# LPCOSensor3vValve.net
KiCad netlist of a schematic drawn in Altium Designer
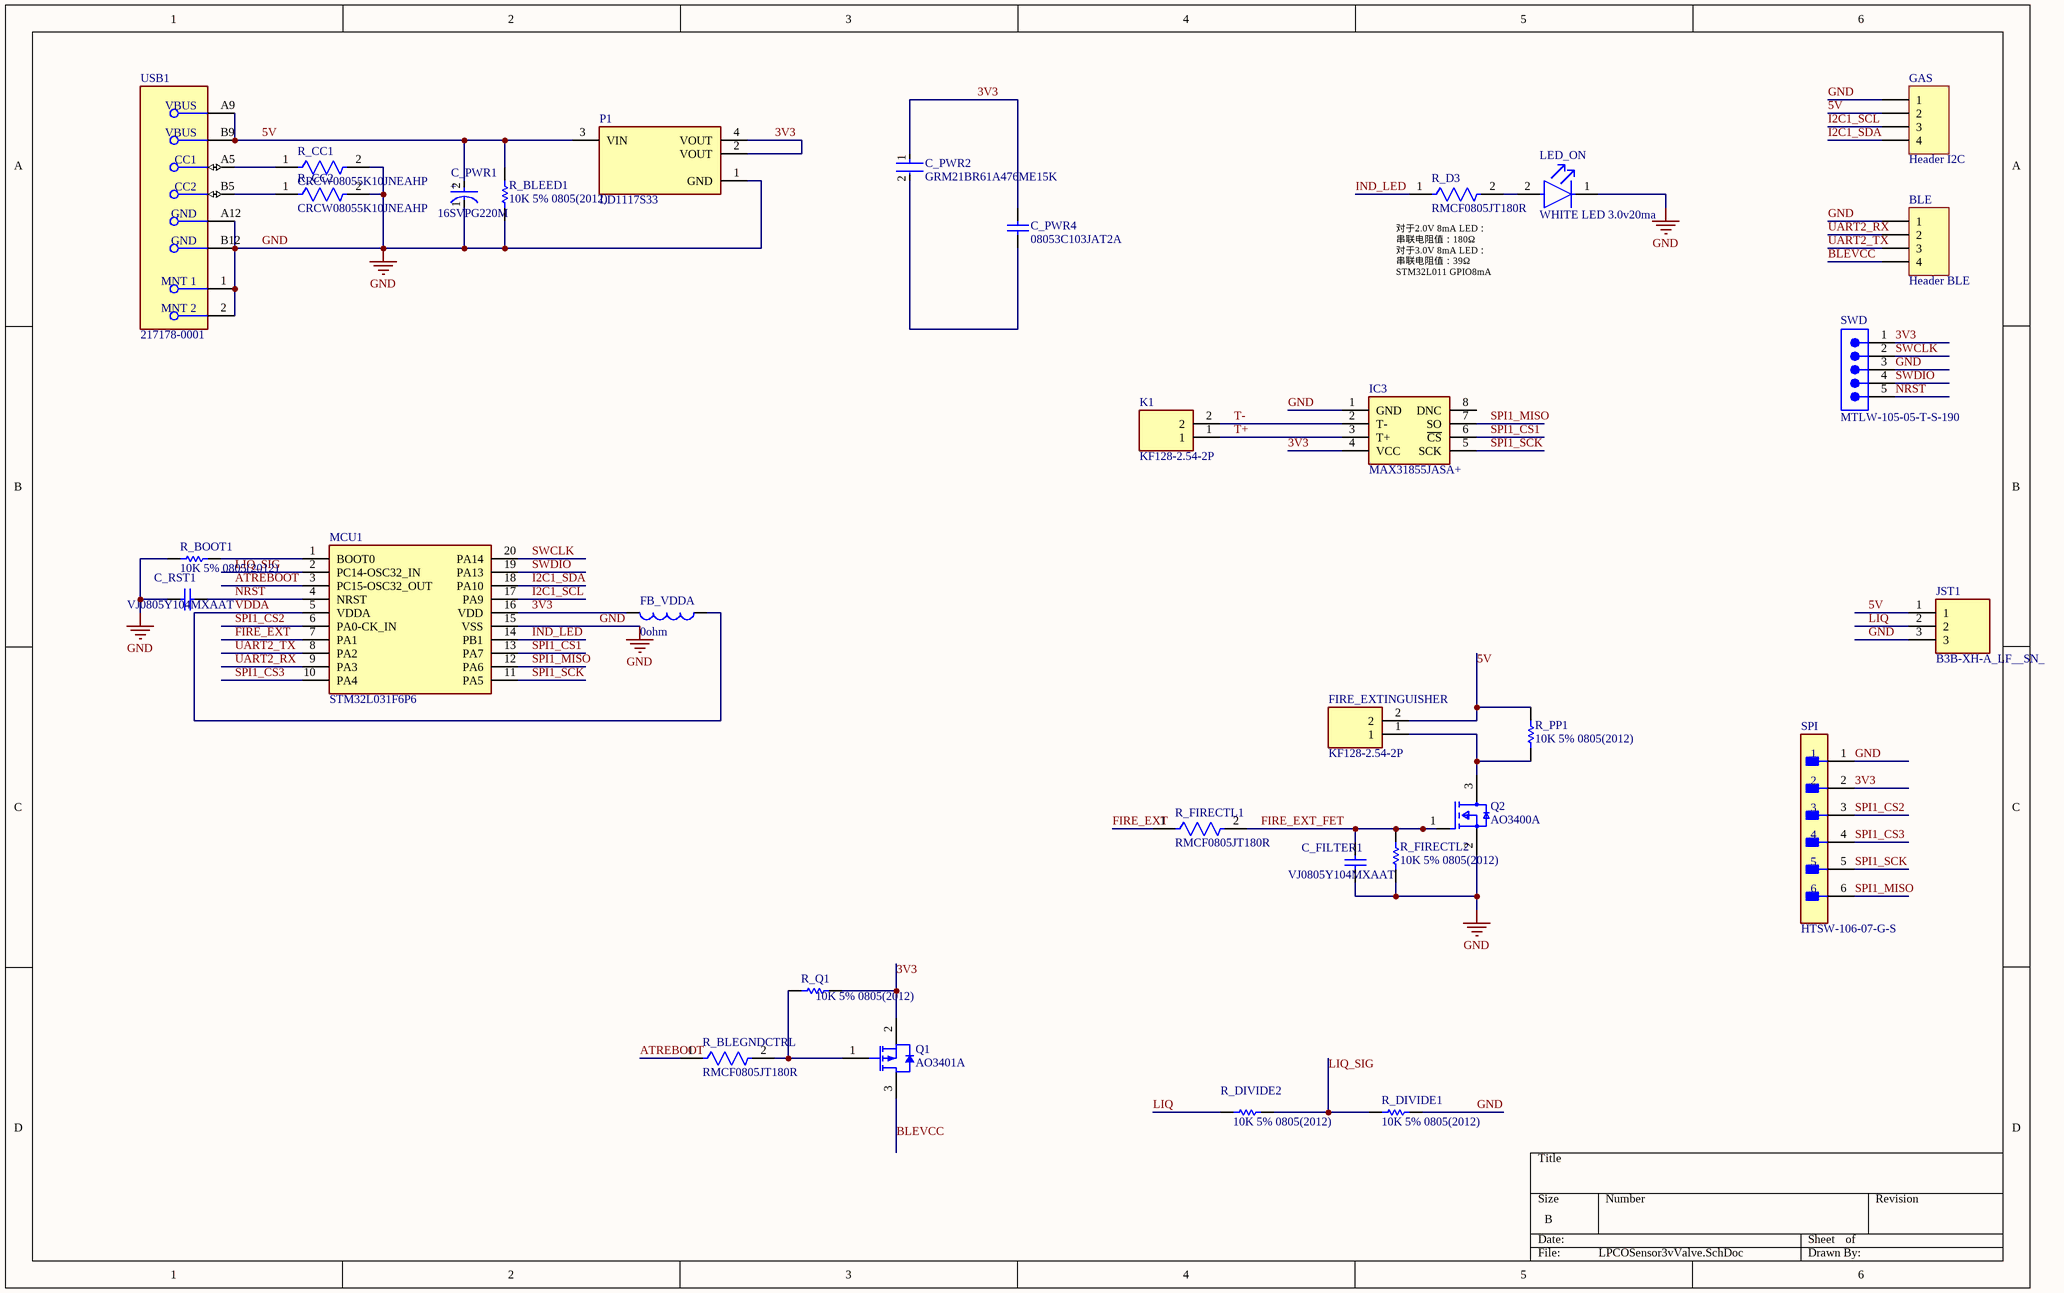
[diagram p0: LPCOSensor3vValve.SchDoc]

(export (version "E")
  (design (tool "Eeschema 10.0.6"))
  (components
    (comp (ref "BLE")
      (value "Header BLE")
      (footprint "HDR1X4")
      (description "Header, 4-Pin")
      (fields (field (name "PUBLISHER") "Altium Limited"))
      (libsource (lib "Miscellaneous Connectors") (part "Header 4"))
    )
    (comp (ref "C_FILTER1")
      (value "VJ0805Y104MXAAT")
      (footprint "CAPC2013X145X48NL20T23")
      (fields (field (name "MANUFACTURER") "Vitramon"))
      (libsource (lib "Altium Content Vault") (part "CAP"))
    )
    (comp (ref "C_PWR1")
      (value "16SVPG220M")
      (footprint "FP-OS-CON-SMT-C6-MFG")
      (description "Conductive Polymer Aluminum Solid Capacitors (OS-CON) 220uF ±20% 16V")
      (libsource (lib "Altium Content Vault") (part "a00bbbee19879c290e62620ae7e47b1"))
    )
    (comp (ref "C_PWR2")
      (value "GRM21BR61A476ME15K")
      (footprint "FP-GRM21B-0_2-e0_2_0_7-IPC_C")
      (description "Chip Multilayer Ceramic Capacitors for General Purpose, 0805, 47uF, X5R, 15%, 20%, 10V")
      (fields (field (name "TOLERANCE") "20%"))
      (libsource (lib "Altium Content Vault") (part "b4654b650e69147ec39a6b967a45e02"))
    )
    (comp (ref "C_PWR4")
      (value "08053C103JAT2A")
      (footprint "CAPC2013X94X50LL20T25")
      (fields (field (name "MANUFACTURER") "AVX Interconnect / Elco"))
      (libsource (lib "Altium Content Vault") (part "CAP"))
    )
    (comp (ref "C_RST1")
      (value "VJ0805Y104MXAAT")
      (footprint "CAPC2013X145X48NL20T23")
      (fields (field (name "MANUFACTURER") "Vitramon"))
      (libsource (lib "Altium Content Vault") (part "CAP"))
    )
    (comp (ref "FB_VDDA")
      (value "0ohm")
      (footprint "WE-CBF_0805_L2W1.2H0.9_HC")
      (fields (field (name "TOLERANCE") "25%"))
      (libsource (lib "Altium Content Vault") (part "Ferrite"))
    )
    (comp (ref "FIRE_EXTINGUISHER")
      (value "KF128-2.54-2P")
      (footprint "SamacSys:KF1282542P")
      (description "Connector")
      (libsource (lib "*") (part "KF128-2.54-2P"))
    )
    (comp (ref "GAS")
      (value "Header I2C")
      (footprint "HDR1X4")
      (description "Header, 4-Pin")
      (fields (field (name "PUBLISHER") "Altium Limited"))
      (libsource (lib "Miscellaneous Connectors") (part "Header 4"))
    )
    (comp (ref "IC3")
      (value "MAX31855JASA+")
      (footprint "SamacSys:SOIC127P600X175-8N")
      (description "Integrated Circuit")
      (fields (field (name "MOUSER PART NUMBER") "700-MAX31855JASA+"))
      (libsource (lib "*") (part "MAX31855JASA+"))
    )
    (comp (ref "JST1")
      (value "B3B-XH-A_LF__SN_")
      (footprint "SamacSys:B3BXHALFSN")
      (description "Connector")
      (fields
        (field (name "MANUFACTURER_PART_NUMBER") "B3B-XH-A(LF)(SN)")
        (field (name "MOUSER PART NUMBER") "306-B3BXHALFSNP")
      )
      (libsource (lib "*") (part "B3B-XH-A_LF__SN_"))
    )
    (comp (ref "K1")
      (value "KF128-2.54-2P")
      (footprint "SamacSys:KF1282542P")
      (description "Connector")
      (libsource (lib "*") (part "KF128-2.54-2P"))
    )
    (comp (ref "LED_ON")
      (value "WHITE LED 3.0v20ma")
      (footprint "FP-SML-LX0805UWC-TR-MFG")
      (description "SML-LX0805UWC-TR White LED, 0805 Diffused, Rectangle Lens SMD package")
      (libsource (lib "Altium Content Vault") (part "8706943c75ba83719d021d2fdc84c58"))
    )
    (comp (ref "MCU1")
      (value "STM32L031F6P6")
      (footprint "SamacSys:SOP65P640X120-20N")
      (description "Integrated Circuit")
      (fields (field (name "MOUSER PART NUMBER") "511-STM32L031F6P6"))
      (libsource (lib "*") (part "STM32L031F6P6"))
    )
    (comp (ref "P1")
      (value "LD1117S33")
      (footprint "FP-SOT-223-0046067_14-MFG")
      (description "IC REG LINEAR 3.3V 800MA SOT223")
      (libsource (lib "Altium Content Vault") (part "7818869c5c16ceab15634627166a29d"))
    )
    (comp (ref "Q1")
      (value "AO3401A")
      (footprint "AO-SOT-23-3L_V")
      (description "P-Channel MOSFET, 30 V, 4 A, -55 to 150 degC, 3-Pin SOT-23-3L, RoHS, Tape and Reel")
      (fields (field (name "MANUFACTURER") "Alpha and Omega"))
      (libsource (lib "Altium Content Vault") (part "PEMOS-GSD-3"))
    )
    (comp (ref "Q2")
      (value "AO3400A")
      (footprint "FP-SOT23-MFG")
      (description "MOSFET N-CH 30V 5.7A SOT23")
      (libsource (lib "Altium Content Vault") (part "0a9ea7c96deaaede766a5b531c28de0"))
    )
    (comp (ref "R_BLEED1")
      (value "10K 5% 0805(2012)")
      (footprint "RESC0805(2012)_L")
      (description "10K 0.125W 5% 0805 (2012 Metric)  SMD")
      (fields (field (name "POWER") "0.125 W") (field (name "TOLERANCE") "5 %"))
      (libsource (lib "Altium Content Vault") (part "RES"))
    )
    (comp (ref "R_BLEGNDCTRL")
      (value "RMCF0805JT180R")
      (footprint "FP-RMCF0805-IPC_B")
      (description "180Ω ±5% 0.125W 0805 Thick Film Chip Resistor AEC-Q200 compliant")
      (fields (field (name "TOLERANCE") "5%"))
      (libsource (lib "Altium Content Vault") (part "1029c3af85768c4190bb7ad29bc67b5"))
    )
    (comp (ref "R_BOOT1")
      (value "10K 5% 0805(2012)")
      (footprint "RESC0805(2012)_L")
      (description "10K 0.125W 5% 0805 (2012 Metric)  SMD")
      (fields (field (name "POWER") "0.125 W") (field (name "TOLERANCE") "5 %"))
      (libsource (lib "Altium Content Vault") (part "RES"))
    )
    (comp (ref "R_CC1")
      (value "CRCW08055K10JNEAHP")
      (footprint "FP-CRCW0805-HPe3-MFG")
      (description "RES Thick Film, 5.1kΩ, 5%, 0.5W, 200ppm/°C, 0805")
      (fields (field (name "TOLERANCE") "5%"))
      (libsource (lib "Altium Content Vault") (part "1029c3af85768c4190bb7ad29bc67b5"))
    )
    (comp (ref "R_CC2")
      (value "CRCW08055K10JNEAHP")
      (footprint "FP-CRCW0805-HPe3-MFG")
      (description "RES Thick Film, 5.1kΩ, 5%, 0.5W, 200ppm/°C, 0805")
      (fields (field (name "TOLERANCE") "5%"))
      (libsource (lib "Altium Content Vault") (part "1029c3af85768c4190bb7ad29bc67b5"))
    )
    (comp (ref "R_D3")
      (value "RMCF0805JT180R")
      (footprint "FP-RMCF0805-IPC_B")
      (description "180Ω ±5% 0.125W 0805 Thick Film Chip Resistor AEC-Q200 compliant")
      (fields (field (name "TOLERANCE") "5%"))
      (libsource (lib "Altium Content Vault") (part "1029c3af85768c4190bb7ad29bc67b5"))
    )
    (comp (ref "R_DIVIDE1")
      (value "10K 5% 0805(2012)")
      (footprint "RESC0805(2012)_L")
      (description "10K 0.125W 5% 0805 (2012 Metric)  SMD")
      (fields (field (name "POWER") "0.125 W") (field (name "TOLERANCE") "5 %"))
      (libsource (lib "Altium Content Vault") (part "RES"))
    )
    (comp (ref "R_DIVIDE2")
      (value "10K 5% 0805(2012)")
      (footprint "RESC0805(2012)_L")
      (description "10K 0.125W 5% 0805 (2012 Metric)  SMD")
      (fields (field (name "POWER") "0.125 W") (field (name "TOLERANCE") "5 %"))
      (libsource (lib "Altium Content Vault") (part "RES"))
    )
    (comp (ref "R_FIRECTL1")
      (value "RMCF0805JT180R")
      (footprint "FP-RMCF0805-IPC_B")
      (description "180Ω ±5% 0.125W 0805 Thick Film Chip Resistor AEC-Q200 compliant")
      (fields (field (name "TOLERANCE") "5%"))
      (libsource (lib "Altium Content Vault") (part "1029c3af85768c4190bb7ad29bc67b5"))
    )
    (comp (ref "R_FIRECTL2")
      (value "10K 5% 0805(2012)")
      (footprint "RESC0805(2012)_L")
      (description "10K 0.125W 5% 0805 (2012 Metric)  SMD")
      (fields (field (name "POWER") "0.125 W") (field (name "TOLERANCE") "5 %"))
      (libsource (lib "Altium Content Vault") (part "RES"))
    )
    (comp (ref "R_PP1")
      (value "10K 5% 0805(2012)")
      (footprint "RESC0805(2012)_L")
      (description "10K 0.125W 5% 0805 (2012 Metric)  SMD")
      (fields (field (name "POWER") "0.125 W") (field (name "TOLERANCE") "5 %"))
      (libsource (lib "Altium Content Vault") (part "RES"))
    )
    (comp (ref "R_Q1")
      (value "10K 5% 0805(2012)")
      (footprint "RESC0805(2012)_L")
      (description "10K 0.125W 5% 0805 (2012 Metric)  SMD")
      (fields (field (name "POWER") "0.125 W") (field (name "TOLERANCE") "5 %"))
      (libsource (lib "Altium Content Vault") (part "RES"))
    )
    (comp (ref "SPI")
      (value "HTSW-106-07-G-S")
      (footprint "FP-HTSW-106-07-G-S-MFG")
      (description "CONN HEADER VERT 6POS 2.54MM")
      (libsource (lib "Altium Content Vault") (part "f2cb566baf1c37ab5a3b8e90bbeafd6"))
    )
    (comp (ref "SWD")
      (value "MTLW-105-05-T-S-190")
      (footprint "SMTC-MTLW-105-05-X-S-190")
      (fields (field (name "MANUFACTURER") "Samtec"))
      (libsource (lib "Altium Content Vault") (part "SMTC-MTLW-105-05-X-S-190"))
    )
    (comp (ref "USB1")
      (value "217178-0001")
      (footprint "FP-217178-0001-MFG")
      (description "CONN RCPT USB2.0 TYP C 24POS SMD")
      (libsource (lib "Altium Content Vault") (part "e5636733757a29d79d1b26da321089d"))
    )
  )
  (nets
    (net (code "1") (name "/3V3") (class "Default")
      (node (ref "C_PWR2") (pin "1") (pinfunction "1_1") (pintype "passive"))
      (node (ref "C_PWR4") (pin "2") (pinfunction "2_2") (pintype "passive"))
      (node (ref "FB_VDDA") (pin "2") (pinfunction "2_2") (pintype "passive"))
      (node (ref "IC3") (pin "4") (pinfunction "VCC_4") (pintype "passive"))
      (node (ref "MCU1") (pin "16") (pinfunction "VDD_16") (pintype "passive"))
      (node (ref "P1") (pin "2") (pinfunction "VOUT_2") (pintype "power_in"))
      (node (ref "P1") (pin "4") (pinfunction "VOUT_4") (pintype "power_in"))
      (node (ref "Q1") (pin "2") (pinfunction "SOURCE_2") (pintype "passive"))
      (node (ref "R_Q1") (pin "1") (pinfunction "1_1") (pintype "passive"))
      (node (ref "SPI") (pin "2") (pinfunction "2_2") (pintype "passive"))
      (node (ref "SWD") (pin "1") (pinfunction "1_1") (pintype "passive"))
    )
    (net (code "2") (name "/5V") (class "Default")
      (node (ref "C_PWR1") (pin "2") (pinfunction "A_2") (pintype "passive"))
      (node (ref "FIRE_EXTINGUISHER") (pin "2") (pinfunction "2_2") (pintype "passive"))
      (node (ref "GAS") (pin "2") (pinfunction "2_2") (pintype "passive"))
      (node (ref "JST1") (pin "1") (pinfunction "1_1") (pintype "passive"))
      (node (ref "P1") (pin "3") (pinfunction "VIN_3") (pintype "power_in"))
      (node (ref "R_BLEED1") (pin "1") (pinfunction "1_1") (pintype "passive"))
      (node (ref "R_PP1") (pin "1") (pinfunction "1_1") (pintype "passive"))
      (node (ref "USB1") (pin "A9") (pinfunction "VBUS_A9") (pintype "power_in"))
      (node (ref "USB1") (pin "B9") (pinfunction "VBUS_B9") (pintype "power_in"))
    )
    (net (code "3") (name "/ATREBOOT") (class "Default")
      (node (ref "MCU1") (pin "3") (pinfunction "PC15-OSC32_OUT_3") (pintype "passive"))
      (node (ref "R_BLEGNDCTRL") (pin "1") (pinfunction "1_1") (pintype "passive"))
    )
    (net (code "4") (name "/BLEVCC") (class "Default")
      (node (ref "BLE") (pin "4") (pinfunction "4_4") (pintype "passive"))
      (node (ref "Q1") (pin "3") (pinfunction "DRAIN_3") (pintype "passive"))
    )
    (net (code "5") (name "/FIRE_EXT") (class "Default")
      (node (ref "MCU1") (pin "7") (pinfunction "PA1_7") (pintype "passive"))
      (node (ref "R_FIRECTL1") (pin "1") (pinfunction "1_1") (pintype "passive"))
    )
    (net (code "6") (name "/FIRE_EXT_FET") (class "Default")
      (node (ref "C_FILTER1") (pin "2") (pinfunction "2_2") (pintype "passive"))
      (node (ref "Q2") (pin "1") (pinfunction "G_1") (pintype "passive"))
      (node (ref "R_FIRECTL1") (pin "2") (pinfunction "2_2") (pintype "passive"))
      (node (ref "R_FIRECTL2") (pin "2") (pinfunction "2_2") (pintype "passive"))
    )
    (net (code "7") (name "/I2C1_SCL") (class "Default")
      (node (ref "GAS") (pin "3") (pinfunction "3_3") (pintype "passive"))
      (node (ref "MCU1") (pin "17") (pinfunction "PA9_17") (pintype "passive"))
    )
    (net (code "8") (name "/I2C1_SDA") (class "Default")
      (node (ref "GAS") (pin "4") (pinfunction "4_4") (pintype "passive"))
      (node (ref "MCU1") (pin "18") (pinfunction "PA10_18") (pintype "passive"))
    )
    (net (code "9") (name "/IND_LED") (class "Default")
      (node (ref "MCU1") (pin "14") (pinfunction "PB1_14") (pintype "passive"))
      (node (ref "R_D3") (pin "1") (pinfunction "1_1") (pintype "passive"))
    )
    (net (code "10") (name "/LIQ") (class "Default")
      (node (ref "JST1") (pin "2") (pinfunction "2_2") (pintype "passive"))
      (node (ref "R_DIVIDE2") (pin "2") (pinfunction "2_2") (pintype "passive"))
    )
    (net (code "11") (name "/LIQ_SIG") (class "Default")
      (node (ref "MCU1") (pin "2") (pinfunction "PC14-OSC32_IN_2") (pintype "passive"))
      (node (ref "R_DIVIDE1") (pin "2") (pinfunction "2_2") (pintype "passive"))
      (node (ref "R_DIVIDE2") (pin "1") (pinfunction "1_1") (pintype "passive"))
    )
    (net (code "12") (name "/NRST") (class "Default")
      (node (ref "C_RST1") (pin "2") (pinfunction "2_2") (pintype "passive"))
      (node (ref "MCU1") (pin "4") (pinfunction "NRST_4") (pintype "passive"))
      (node (ref "SWD") (pin "5") (pinfunction "5_5") (pintype "passive"))
    )
    (net (code "13") (name "/SPI1_CS1") (class "Default")
      (node (ref "IC3") (pin "6") (pinfunction "~{CS}_6") (pintype "passive"))
      (node (ref "MCU1") (pin "13") (pinfunction "PA7_13") (pintype "passive"))
    )
    (net (code "14") (name "/SPI1_CS2") (class "Default")
      (node (ref "MCU1") (pin "6") (pinfunction "PA0-CK_IN_6") (pintype "passive"))
      (node (ref "SPI") (pin "3") (pinfunction "3_3") (pintype "passive"))
    )
    (net (code "15") (name "/SPI1_CS3") (class "Default")
      (node (ref "MCU1") (pin "10") (pinfunction "PA4_10") (pintype "passive"))
      (node (ref "SPI") (pin "4") (pinfunction "4_4") (pintype "passive"))
    )
    (net (code "16") (name "/SPI1_MISO") (class "Default")
      (node (ref "IC3") (pin "7") (pinfunction "SO_7") (pintype "passive"))
      (node (ref "MCU1") (pin "12") (pinfunction "PA6_12") (pintype "passive"))
      (node (ref "SPI") (pin "6") (pinfunction "6_6") (pintype "passive"))
    )
    (net (code "17") (name "/SPI1_SCK") (class "Default")
      (node (ref "IC3") (pin "5") (pinfunction "SCK_5") (pintype "passive"))
      (node (ref "MCU1") (pin "11") (pinfunction "PA5_11") (pintype "passive"))
      (node (ref "SPI") (pin "5") (pinfunction "5_5") (pintype "passive"))
    )
    (net (code "18") (name "/SWCLK") (class "Default")
      (node (ref "MCU1") (pin "20") (pinfunction "PA14_20") (pintype "passive"))
      (node (ref "SWD") (pin "2") (pinfunction "2_2") (pintype "passive"))
    )
    (net (code "19") (name "/SWDIO") (class "Default")
      (node (ref "MCU1") (pin "19") (pinfunction "PA13_19") (pintype "passive"))
      (node (ref "SWD") (pin "4") (pinfunction "4_4") (pintype "passive"))
    )
    (net (code "20") (name "/T+") (class "Default")
      (node (ref "IC3") (pin "3") (pinfunction "T+_3") (pintype "passive"))
      (node (ref "K1") (pin "1") (pinfunction "1_1") (pintype "passive"))
    )
    (net (code "21") (name "/T-") (class "Default")
      (node (ref "IC3") (pin "2") (pinfunction "T-_2") (pintype "passive"))
      (node (ref "K1") (pin "2") (pinfunction "2_2") (pintype "passive"))
    )
    (net (code "22") (name "/UART2_RX") (class "Default")
      (node (ref "BLE") (pin "2") (pinfunction "2_2") (pintype "passive"))
      (node (ref "MCU1") (pin "9") (pinfunction "PA3_9") (pintype "passive"))
    )
    (net (code "23") (name "/UART2_TX") (class "Default")
      (node (ref "BLE") (pin "3") (pinfunction "3_3") (pintype "passive"))
      (node (ref "MCU1") (pin "8") (pinfunction "PA2_8") (pintype "passive"))
    )
    (net (code "24") (name "/VDDA") (class "Default")
      (node (ref "FB_VDDA") (pin "1") (pinfunction "1_1") (pintype "passive"))
      (node (ref "MCU1") (pin "5") (pinfunction "VDDA_5") (pintype "passive"))
    )
    (net (code "25") (name "GND") (class "Default")
      (node (ref "BLE") (pin "1") (pinfunction "1_1") (pintype "passive"))
      (node (ref "C_FILTER1") (pin "1") (pinfunction "1_1") (pintype "passive"))
      (node (ref "C_PWR1") (pin "1") (pinfunction "C_1") (pintype "passive"))
      (node (ref "C_RST1") (pin "1") (pinfunction "1_1") (pintype "passive"))
      (node (ref "GAS") (pin "1") (pinfunction "1_1") (pintype "passive"))
      (node (ref "IC3") (pin "1") (pinfunction "GND_1") (pintype "passive"))
      (node (ref "JST1") (pin "3") (pinfunction "3_3") (pintype "passive"))
      (node (ref "LED_ON") (pin "1") (pinfunction "C_1") (pintype "passive"))
      (node (ref "MCU1") (pin "15") (pinfunction "VSS_15") (pintype "passive"))
      (node (ref "P1") (pin "1") (pinfunction "GND_1") (pintype "power_in"))
      (node (ref "Q2") (pin "2") (pinfunction "S_2") (pintype "passive"))
      (node (ref "R_BLEED1") (pin "2") (pinfunction "2_2") (pintype "passive"))
      (node (ref "R_BOOT1") (pin "2") (pinfunction "2_2") (pintype "passive"))
      (node (ref "R_CC1") (pin "2") (pinfunction "2_2") (pintype "passive"))
      (node (ref "R_CC2") (pin "2") (pinfunction "2_2") (pintype "passive"))
      (node (ref "R_DIVIDE1") (pin "1") (pinfunction "1_1") (pintype "passive"))
      (node (ref "R_FIRECTL2") (pin "1") (pinfunction "1_1") (pintype "passive"))
      (node (ref "SPI") (pin "1") (pinfunction "1_1") (pintype "passive"))
      (node (ref "SWD") (pin "3") (pinfunction "3_3") (pintype "passive"))
      (node (ref "USB1") (pin "1") (pinfunction "MNT_1_1") (pintype "passive"))
      (node (ref "USB1") (pin "2") (pinfunction "MNT_2_2") (pintype "passive"))
      (node (ref "USB1") (pin "A12") (pinfunction "GND_A12") (pintype "power_in"))
      (node (ref "USB1") (pin "B12") (pinfunction "GND_B12") (pintype "power_in"))
    )
    (net (code "26") (name "Net-(C_PWR2-Pad2)") (class "Default")
      (node (ref "C_PWR2") (pin "2") (pinfunction "2_2") (pintype "passive"))
      (node (ref "C_PWR4") (pin "1") (pinfunction "1_1") (pintype "passive"))
    )
    (net (code "27") (name "Net-(LED_ON-A)") (class "Default")
      (node (ref "LED_ON") (pin "2") (pinfunction "A_2") (pintype "passive"))
      (node (ref "R_D3") (pin "2") (pinfunction "2_2") (pintype "passive"))
    )
    (net (code "28") (name "Net-(MCU1-BOOT0)") (class "Default")
      (node (ref "MCU1") (pin "1") (pinfunction "BOOT0_1") (pintype "passive"))
      (node (ref "R_BOOT1") (pin "1") (pinfunction "1_1") (pintype "passive"))
    )
    (net (code "29") (name "Net-(Q1-GATE)") (class "Default")
      (node (ref "Q1") (pin "1") (pinfunction "GATE_1") (pintype "passive"))
      (node (ref "R_BLEGNDCTRL") (pin "2") (pinfunction "2_2") (pintype "passive"))
      (node (ref "R_Q1") (pin "2") (pinfunction "2_2") (pintype "passive"))
    )
    (net (code "30") (name "Net-(Q2-D)") (class "Default")
      (node (ref "FIRE_EXTINGUISHER") (pin "1") (pinfunction "1_1") (pintype "passive"))
      (node (ref "Q2") (pin "3") (pinfunction "D_3") (pintype "passive"))
      (node (ref "R_PP1") (pin "2") (pinfunction "2_2") (pintype "passive"))
    )
    (net (code "31") (name "Net-(USB1-CC1)") (class "Default")
      (node (ref "R_CC1") (pin "1") (pinfunction "1_1") (pintype "passive"))
      (node (ref "USB1") (pin "A5") (pinfunction "CC1_A5") (pintype "bidirectional"))
    )
    (net (code "32") (name "Net-(USB1-CC2)") (class "Default")
      (node (ref "R_CC2") (pin "1") (pinfunction "1_1") (pintype "passive"))
      (node (ref "USB1") (pin "B5") (pinfunction "CC2_B5") (pintype "bidirectional"))
    )
    (net (code "33") (name "unconnected-(IC3-DNC-Pad8)") (class "Default")
      (node (ref "IC3") (pin "8") (pinfunction "DNC_8") (pintype "passive"))
    )
  )
)
